# Schematic.net
KiCad netlist of a schematic drawn in Altium Designer
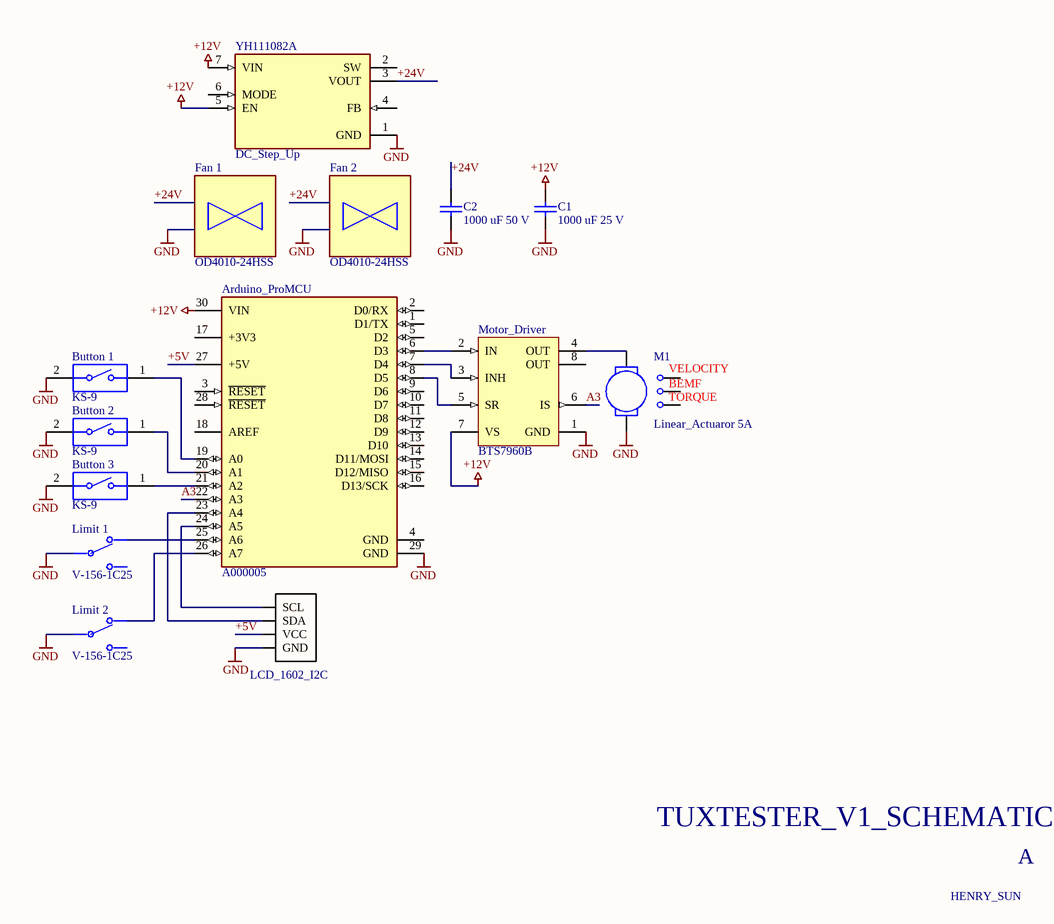
[diagram p0: Schematic.SchDoc]

(export (version "E")
  (design (tool "Eeschema 10.0.6"))
  (components
    (comp (ref "Arduino_ProMCU")
      (value "A000005")
      (footprint "FP-A000005-MFG")
      (description "ARDUINO NANO ATMEGA328 EVAL BRD")
      (libsource (lib "Altium Content Vault") (part "d190c066e99afd1c6882cf92e11b2cc"))
    )
    (comp (ref "Button 1")
      (value "KS-9")
      (footprint "CHRY-MX1A-11NN_V")
      (description "Keymodule MX, SPST, IP40, 12 V Max, 10 mA Max, -10 to 70 degC, 2-Pin THD, RoHS, Bulk")
      (fields (field (name "PART NO") "MX1A11NN") (field (name "MANUFACTURER") "Cherry"))
      (libsource (lib "Altium Content Vault") (part "KEYSW-SPST-2"))
    )
    (comp (ref "Button 2")
      (value "KS-9")
      (footprint "CHRY-MX1A-11NN_V")
      (description "Keymodule MX, SPST, IP40, 12 V Max, 10 mA Max, -10 to 70 degC, 2-Pin THD, RoHS, Bulk")
      (fields (field (name "PART NO") "MX1A11NN") (field (name "MANUFACTURER") "Cherry"))
      (libsource (lib "Altium Content Vault") (part "KEYSW-SPST-2"))
    )
    (comp (ref "Button 3")
      (value "KS-9")
      (footprint "CHRY-MX1A-11NN_V")
      (description "Keymodule MX, SPST, IP40, 12 V Max, 10 mA Max, -10 to 70 degC, 2-Pin THD, RoHS, Bulk")
      (fields (field (name "PART NO") "MX1A11NN") (field (name "MANUFACTURER") "Cherry"))
      (libsource (lib "Altium Content Vault") (part "KEYSW-SPST-2"))
    )
    (comp (ref "C1")
      (value "1000 uF 25 V")
      (description "Capacitor")
      (libsource (lib "Simulation Generic Components") (part "Capacitor"))
    )
    (comp (ref "C2")
      (value "1000 uF 50 V")
      (description "Capacitor")
      (libsource (lib "Simulation Generic Components") (part "Capacitor"))
    )
    (comp (ref "DC_Step_Up")
      (value "YH111082A")
      (footprint "CONV_TPS61022RWUT")
      (fields (field (name "MF") "Texas Instruments") (field (name "MP") "TPS61022RWUT"))
      (libsource (lib "TPS61022RWUT") (part "TPS61022RWUT"))
    )
    (comp (ref "Fan 1")
      (value "OD4010-24HSS")
      (footprint "FP-PFB1224UHE-MFG")
      (description "FAN AXIAL 120X38MM 24VDC WIRE")
      (libsource (lib "Altium Content Vault") (part "9c7c42b40ec000def08324f3a61b975"))
    )
    (comp (ref "Fan 2")
      (value "OD4010-24HSS")
      (footprint "FP-PFB1224UHE-MFG")
      (description "FAN AXIAL 120X38MM 24VDC WIRE")
      (libsource (lib "Altium Content Vault") (part "9c7c42b40ec000def08324f3a61b975"))
    )
    (comp (ref "LCD_1602_I2C")
      (value "LCD1602")
      (footprint "LCD1602_I2CLCD1602_LCD1602(Primary)")
      (description "BLUE LCD 1602 2x16 Character Mat")
      (fields (field (name "MF") "kamami"))
      (libsource (lib "LCD1602") (part "LCD1602"))
    )
    (comp (ref "Limit 1")
      (value "V-156-1C25")
      (footprint "FP-V-155-1A5-MFG")
      (description "SWITCH SNAP ACTION SPDT 15A 250V")
      (libsource (lib "Altium Content Vault") (part "3e9884f9922fbfe170c5e5196286929"))
    )
    (comp (ref "Limit 2")
      (value "V-156-1C25")
      (footprint "FP-V-155-1A5-MFG")
      (description "SWITCH SNAP ACTION SPDT 15A 250V")
      (libsource (lib "Altium Content Vault") (part "3e9884f9922fbfe170c5e5196286929"))
    )
    (comp (ref "M1")
      (value "Linear_Actuaror 5A")
      (description "DC Motor")
      (libsource (lib "Simulation Generic Components") (part "DC Motor"))
    )
    (comp (ref "Motor_Driver")
      (value "BTS7960B")
      (footprint "INF-P-TO-263-7-6_M")
      (description "High Current PN Half Bridge NovalithIC, -40 to 150 degC, P-TO-263-7-6")
      (fields (field (name "MANUFACTURER") "Infineon"))
      (libsource (lib "Altium Content Vault") (part "INF-BTS7960B-P-TO-263-7-8"))
    )
  )
  (nets
    (net (code "1") (name "+12V") (class "Default")
      (node (ref "Arduino_ProMCU") (pin "30") (pinfunction "VIN_30") (pintype "power_in"))
      (node (ref "C1") (pin "1") (pinfunction "1_1") (pintype "passive"))
      (node (ref "DC_Step_Up") (pin "5") (pinfunction "EN_5") (pintype "input"))
      (node (ref "DC_Step_Up") (pin "7") (pinfunction "VIN_7") (pintype "input"))
      (node (ref "Motor_Driver") (pin "7") (pinfunction "VS_7") (pintype "power_in"))
    )
    (net (code "2") (name "/+5V") (class "Default")
      (node (ref "Arduino_ProMCU") (pin "27") (pinfunction "+5V_27") (pintype "power_in"))
      (node (ref "LCD_1602_I2C") (pin "P$2") (pinfunction "VCC_P$2") (pintype "bidirectional"))
    )
    (net (code "3") (name "/+24V") (class "Default")
      (node (ref "C2") (pin "1") (pinfunction "1_1") (pintype "passive"))
      (node (ref "DC_Step_Up") (pin "3") (pinfunction "VOUT_3") (pintype "power_in"))
    )
    (net (code "4") (name "/A3") (class "Default")
      (node (ref "Arduino_ProMCU") (pin "22") (pinfunction "A3_22") (pintype "bidirectional"))
      (node (ref "Motor_Driver") (pin "6") (pinfunction "IS_6") (pintype "output"))
    )
    (net (code "5") (name "GND") (class "Default")
      (node (ref "Arduino_ProMCU") (pin "29") (pinfunction "GND_29") (pintype "power_in"))
      (node (ref "Button 1") (pin "2") (pinfunction "2_2") (pintype "passive"))
      (node (ref "Button 2") (pin "2") (pinfunction "2_2") (pintype "passive"))
      (node (ref "Button 3") (pin "2") (pinfunction "2_2") (pintype "passive"))
      (node (ref "C1") (pin "2") (pinfunction "2_2") (pintype "passive"))
      (node (ref "C2") (pin "2") (pinfunction "2_2") (pintype "passive"))
      (node (ref "DC_Step_Up") (pin "1") (pinfunction "GND_1") (pintype "power_in"))
      (node (ref "LCD_1602_I2C") (pin "P$1") (pinfunction "GND_P$1") (pintype "bidirectional"))
      (node (ref "M1") (pin "2") (pinfunction "2_2") (pintype "passive"))
      (node (ref "Motor_Driver") (pin "1") (pinfunction "GND_1") (pintype "power_in"))
    )
    (net (code "6") (name "Net-(Arduino_ProMCU-A0)") (class "Default")
      (node (ref "Arduino_ProMCU") (pin "19") (pinfunction "A0_19") (pintype "bidirectional"))
      (node (ref "Button 1") (pin "1") (pinfunction "1_1") (pintype "passive"))
    )
    (net (code "7") (name "Net-(Arduino_ProMCU-A1)") (class "Default")
      (node (ref "Arduino_ProMCU") (pin "20") (pinfunction "A1_20") (pintype "bidirectional"))
      (node (ref "Button 2") (pin "1") (pinfunction "1_1") (pintype "passive"))
    )
    (net (code "8") (name "Net-(Arduino_ProMCU-A2)") (class "Default")
      (node (ref "Arduino_ProMCU") (pin "21") (pinfunction "A2_21") (pintype "bidirectional"))
      (node (ref "Button 3") (pin "1") (pinfunction "1_1") (pintype "passive"))
    )
    (net (code "9") (name "Net-(Arduino_ProMCU-A4)") (class "Default")
      (node (ref "Arduino_ProMCU") (pin "23") (pinfunction "A4_23") (pintype "bidirectional"))
      (node (ref "LCD_1602_I2C") (pin "P$3") (pinfunction "SDA_P$3") (pintype "bidirectional"))
    )
    (net (code "10") (name "Net-(Arduino_ProMCU-A5)") (class "Default")
      (node (ref "Arduino_ProMCU") (pin "24") (pinfunction "A5_24") (pintype "bidirectional"))
      (node (ref "LCD_1602_I2C") (pin "P$4") (pinfunction "SCL_P$4") (pintype "bidirectional"))
    )
    (net (code "11") (name "Net-(Arduino_ProMCU-D3)") (class "Default")
      (node (ref "Arduino_ProMCU") (pin "6") (pinfunction "D3_6") (pintype "bidirectional"))
      (node (ref "Motor_Driver") (pin "2") (pinfunction "IN_2") (pintype "input"))
    )
    (net (code "12") (name "Net-(Arduino_ProMCU-D4)") (class "Default")
      (node (ref "Arduino_ProMCU") (pin "7") (pinfunction "D4_7") (pintype "bidirectional"))
      (node (ref "Motor_Driver") (pin "3") (pinfunction "INH_3") (pintype "input"))
    )
    (net (code "13") (name "Net-(Arduino_ProMCU-D5)") (class "Default")
      (node (ref "Arduino_ProMCU") (pin "8") (pinfunction "D5_8") (pintype "bidirectional"))
      (node (ref "Motor_Driver") (pin "5") (pinfunction "SR_5") (pintype "input"))
    )
    (net (code "14") (name "Net-(M1-Pad1)") (class "Default")
      (node (ref "M1") (pin "1") (pinfunction "1_1") (pintype "passive"))
      (node (ref "Motor_Driver") (pin "4") (pinfunction "OUT_4") (pintype "power_in"))
    )
    (net (code "15") (name "unconnected-(Arduino_ProMCU-+3V3-Pad17)") (class "Default")
      (node (ref "Arduino_ProMCU") (pin "17") (pinfunction "+3V3_17") (pintype "power_in"))
    )
    (net (code "16") (name "unconnected-(Arduino_ProMCU-A6-Pad25)") (class "Default")
      (node (ref "Arduino_ProMCU") (pin "25") (pinfunction "A6_25") (pintype "bidirectional"))
    )
    (net (code "17") (name "unconnected-(Arduino_ProMCU-A7-Pad26)") (class "Default")
      (node (ref "Arduino_ProMCU") (pin "26") (pinfunction "A7_26") (pintype "bidirectional"))
    )
    (net (code "18") (name "unconnected-(Arduino_ProMCU-AREF-Pad18)") (class "Default")
      (node (ref "Arduino_ProMCU") (pin "18") (pinfunction "AREF_18") (pintype "passive"))
    )
    (net (code "19") (name "unconnected-(Arduino_ProMCU-D0{slash}RX-Pad2)") (class "Default")
      (node (ref "Arduino_ProMCU") (pin "2") (pinfunction "D0/RX_2") (pintype "bidirectional"))
    )
    (net (code "20") (name "unconnected-(Arduino_ProMCU-D1{slash}TX-Pad1)") (class "Default")
      (node (ref "Arduino_ProMCU") (pin "1") (pinfunction "D1/TX_1") (pintype "bidirectional"))
    )
    (net (code "21") (name "unconnected-(Arduino_ProMCU-D2-Pad5)") (class "Default")
      (node (ref "Arduino_ProMCU") (pin "5") (pinfunction "D2_5") (pintype "bidirectional"))
    )
    (net (code "22") (name "unconnected-(Arduino_ProMCU-D6-Pad9)") (class "Default")
      (node (ref "Arduino_ProMCU") (pin "9") (pinfunction "D6_9") (pintype "bidirectional"))
    )
    (net (code "23") (name "unconnected-(Arduino_ProMCU-D7-Pad10)") (class "Default")
      (node (ref "Arduino_ProMCU") (pin "10") (pinfunction "D7_10") (pintype "bidirectional"))
    )
    (net (code "24") (name "unconnected-(Arduino_ProMCU-D8-Pad11)") (class "Default")
      (node (ref "Arduino_ProMCU") (pin "11") (pinfunction "D8_11") (pintype "bidirectional"))
    )
    (net (code "25") (name "unconnected-(Arduino_ProMCU-D9-Pad12)") (class "Default")
      (node (ref "Arduino_ProMCU") (pin "12") (pinfunction "D9_12") (pintype "bidirectional"))
    )
    (net (code "26") (name "unconnected-(Arduino_ProMCU-D10-Pad13)") (class "Default")
      (node (ref "Arduino_ProMCU") (pin "13") (pinfunction "D10_13") (pintype "bidirectional"))
    )
    (net (code "27") (name "unconnected-(Arduino_ProMCU-D11{slash}MOSI-Pad14)") (class "Default")
      (node (ref "Arduino_ProMCU") (pin "14") (pinfunction "D11/MOSI_14") (pintype "bidirectional"))
    )
    (net (code "28") (name "unconnected-(Arduino_ProMCU-D12{slash}MISO-Pad15)") (class "Default")
      (node (ref "Arduino_ProMCU") (pin "15") (pinfunction "D12/MISO_15") (pintype "bidirectional"))
    )
    (net (code "29") (name "unconnected-(Arduino_ProMCU-D13{slash}SCK-Pad16)") (class "Default")
      (node (ref "Arduino_ProMCU") (pin "16") (pinfunction "D13/SCK_16") (pintype "bidirectional"))
    )
    (net (code "30") (name "unconnected-(Arduino_ProMCU-GND-Pad4)") (class "Default")
      (node (ref "Arduino_ProMCU") (pin "4") (pinfunction "GND_4") (pintype "power_in"))
    )
    (net (code "31") (name "unconnected-(Arduino_ProMCU-~{RESET}-Pad3)") (class "Default")
      (node (ref "Arduino_ProMCU") (pin "3") (pinfunction "~{RESET}_3") (pintype "input"))
    )
    (net (code "32") (name "unconnected-(Arduino_ProMCU-~{RESET}-Pad28)") (class "Default")
      (node (ref "Arduino_ProMCU") (pin "28") (pinfunction "~{RESET}_28") (pintype "input"))
    )
    (net (code "33") (name "unconnected-(DC_Step_Up-FB-Pad4)") (class "Default")
      (node (ref "DC_Step_Up") (pin "4") (pinfunction "FB_4") (pintype "input"))
    )
    (net (code "34") (name "unconnected-(DC_Step_Up-MODE-Pad6)") (class "Default")
      (node (ref "DC_Step_Up") (pin "6") (pinfunction "MODE_6") (pintype "input"))
    )
    (net (code "35") (name "unconnected-(DC_Step_Up-SW-Pad2)") (class "Default")
      (node (ref "DC_Step_Up") (pin "2") (pinfunction "SW_2") (pintype "power_in"))
    )
    (net (code "36") (name "unconnected-(M1-Pad3)") (class "Default")
      (node (ref "M1") (pin "3") (pinfunction "3_3") (pintype "passive"))
    )
    (net (code "37") (name "unconnected-(M1-Pad4)") (class "Default")
      (node (ref "M1") (pin "4") (pinfunction "4_4") (pintype "passive"))
    )
    (net (code "38") (name "unconnected-(M1-Pad5)") (class "Default")
      (node (ref "M1") (pin "5") (pinfunction "5_5") (pintype "passive"))
    )
    (net (code "39") (name "unconnected-(Motor_Driver-OUT-Pad8)") (class "Default")
      (node (ref "Motor_Driver") (pin "8") (pinfunction "OUT_8") (pintype "power_in"))
    )
  )
)
